# MT32Pi_lite.net
KiCad netlist of a schematic drawn in Altium Designer
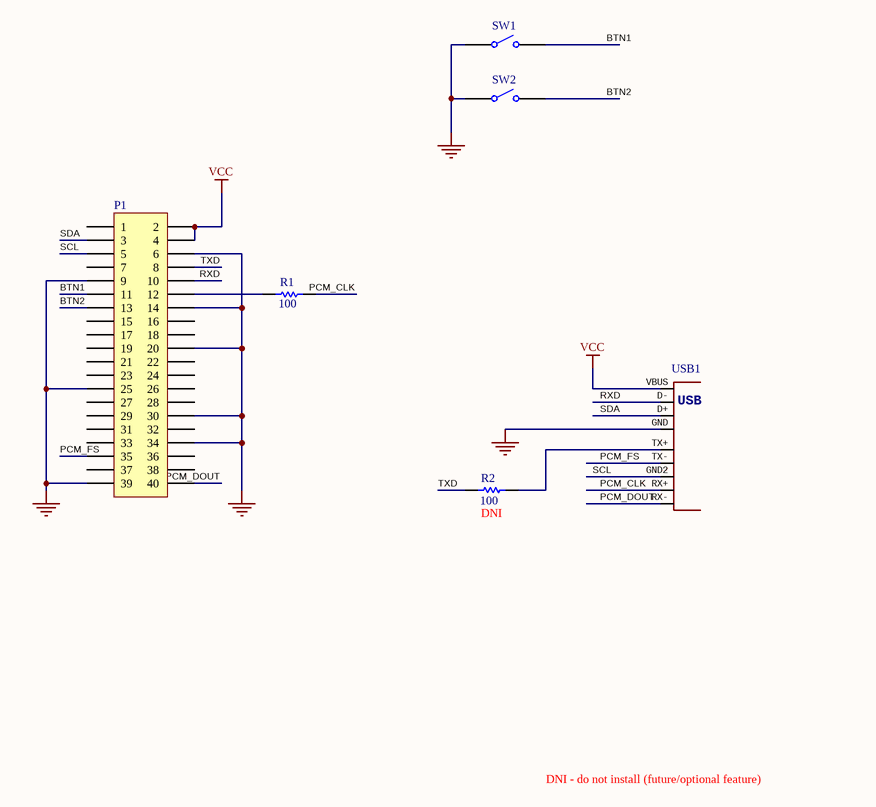
[diagram p0: MT32Pi_lite.SchDoc]

(export (version "E")
  (design (tool "Eeschema 10.0.6"))
  (components
    (comp (ref "P1")
      (value "Header 20X2")
      (footprint "HDR20x2")
      (description "Header, 20-Pin, Dual row")
      (fields (field (name "PUBLISHER") "Altium Limited"))
      (libsource (lib "Miscellaneous Connectors") (part "Header 20X2"))
    )
    (comp (ref "R1")
      (value "100")
      (footprint "R0805")
      (fields (field (name "PUBLISHER") "Altium Limited"))
      (libsource (lib "lib") (part "R0805"))
    )
    (comp (ref "R2")
      (value "100")
      (footprint "R0805 - DNI")
      (fields (field (name "PUBLISHER") "Altium Limited"))
      (libsource (lib "lib") (part "R0805 - DNI"))
    )
    (comp (ref "SW1")
      (value "Tact_60X35")
      (footprint "TACT_60X35")
      (description "Tact 6.0mm X 3.5mm")
      (fields (field (name "PARTNUMBER") "434111050826"))
      (libsource (lib "lib") (part "Tact_60X35"))
    )
    (comp (ref "SW2")
      (value "Tact_60X35")
      (footprint "TACT_60X35")
      (description "Tact 6.0mm X 3.5mm")
      (fields (field (name "PARTNUMBER") "434111050826"))
      (libsource (lib "lib") (part "Tact_60X35"))
    )
    (comp (ref "USB1")
      (value "USBA30-PTH")
      (footprint "USB3-A-M-PTH")
      (fields (field (name "USB") "USB"))
      (libsource (lib "lib") (part "USBA30-PTH"))
    )
  )
  (nets
    (net (code "1") (name "/BTN1") (class "Default")
      (node (ref "P1") (pin "11") (pinfunction "11_11") (pintype "passive"))
      (node (ref "SW1") (pin "2") (pinfunction "2_2") (pintype "passive"))
    )
    (net (code "2") (name "/BTN2") (class "Default")
      (node (ref "P1") (pin "13") (pinfunction "13_13") (pintype "passive"))
      (node (ref "SW2") (pin "2") (pinfunction "2_2") (pintype "passive"))
    )
    (net (code "3") (name "/PCM_CLK") (class "Default")
      (node (ref "R1") (pin "1") (pinfunction "1_1") (pintype "passive"))
      (node (ref "USB1") (pin "RX+") (pinfunction "RX+_RX+") (pintype "passive"))
    )
    (net (code "4") (name "/PCM_DOUT") (class "Default")
      (node (ref "P1") (pin "40") (pinfunction "40_40") (pintype "passive"))
      (node (ref "USB1") (pin "RX-") (pinfunction "RX-_RX-") (pintype "passive"))
    )
    (net (code "5") (name "/PCM_FS") (class "Default")
      (node (ref "P1") (pin "35") (pinfunction "35_35") (pintype "passive"))
      (node (ref "USB1") (pin "TX-") (pinfunction "TX-_TX-") (pintype "passive"))
    )
    (net (code "6") (name "/RXD") (class "Default")
      (node (ref "P1") (pin "10") (pinfunction "10_10") (pintype "passive"))
      (node (ref "USB1") (pin "D-") (pinfunction "D-_D-") (pintype "passive"))
    )
    (net (code "7") (name "/SCL") (class "Default")
      (node (ref "P1") (pin "5") (pinfunction "5_5") (pintype "passive"))
      (node (ref "USB1") (pin "GND2") (pinfunction "GND2_GND2") (pintype "passive"))
    )
    (net (code "8") (name "/SDA") (class "Default")
      (node (ref "P1") (pin "3") (pinfunction "3_3") (pintype "passive"))
      (node (ref "USB1") (pin "D+") (pinfunction "D+_D+") (pintype "passive"))
    )
    (net (code "9") (name "/TXD") (class "Default")
      (node (ref "P1") (pin "8") (pinfunction "8_8") (pintype "passive"))
      (node (ref "R2") (pin "1") (pinfunction "1_1") (pintype "passive"))
    )
    (net (code "10") (name "GND") (class "Default")
      (node (ref "P1") (pin "14") (pinfunction "14_14") (pintype "passive"))
      (node (ref "P1") (pin "20") (pinfunction "20_20") (pintype "passive"))
      (node (ref "P1") (pin "25") (pinfunction "25_25") (pintype "passive"))
      (node (ref "P1") (pin "30") (pinfunction "30_30") (pintype "passive"))
      (node (ref "P1") (pin "34") (pinfunction "34_34") (pintype "passive"))
      (node (ref "P1") (pin "39") (pinfunction "39_39") (pintype "passive"))
      (node (ref "P1") (pin "6") (pinfunction "6_6") (pintype "passive"))
      (node (ref "P1") (pin "9") (pinfunction "9_9") (pintype "passive"))
      (node (ref "SW1") (pin "1") (pinfunction "1_1") (pintype "passive"))
      (node (ref "SW2") (pin "1") (pinfunction "1_1") (pintype "passive"))
      (node (ref "USB1") (pin "GND") (pinfunction "GND_GND") (pintype "passive"))
    )
    (net (code "11") (name "Net-(P1-Pad12)") (class "Default")
      (node (ref "P1") (pin "12") (pinfunction "12_12") (pintype "passive"))
      (node (ref "R1") (pin "2") (pinfunction "2_2") (pintype "passive"))
    )
    (net (code "12") (name "Net-(R2-Pad2)") (class "Default")
      (node (ref "R2") (pin "2") (pinfunction "2_2") (pintype "passive"))
      (node (ref "USB1") (pin "TX+") (pinfunction "TX+_TX+") (pintype "passive"))
    )
    (net (code "13") (name "VCC") (class "Default")
      (node (ref "P1") (pin "2") (pinfunction "2_2") (pintype "passive"))
      (node (ref "P1") (pin "4") (pinfunction "4_4") (pintype "passive"))
      (node (ref "USB1") (pin "VBUS") (pinfunction "VBUS_VBUS") (pintype "passive"))
    )
    (net (code "14") (name "unconnected-(P1-Pad1)") (class "Default")
      (node (ref "P1") (pin "1") (pinfunction "1_1") (pintype "passive"))
    )
    (net (code "15") (name "unconnected-(P1-Pad7)") (class "Default")
      (node (ref "P1") (pin "7") (pinfunction "7_7") (pintype "passive"))
    )
    (net (code "16") (name "unconnected-(P1-Pad15)") (class "Default")
      (node (ref "P1") (pin "15") (pinfunction "15_15") (pintype "passive"))
    )
    (net (code "17") (name "unconnected-(P1-Pad16)") (class "Default")
      (node (ref "P1") (pin "16") (pinfunction "16_16") (pintype "passive"))
    )
    (net (code "18") (name "unconnected-(P1-Pad17)") (class "Default")
      (node (ref "P1") (pin "17") (pinfunction "17_17") (pintype "passive"))
    )
    (net (code "19") (name "unconnected-(P1-Pad18)") (class "Default")
      (node (ref "P1") (pin "18") (pinfunction "18_18") (pintype "passive"))
    )
    (net (code "20") (name "unconnected-(P1-Pad19)") (class "Default")
      (node (ref "P1") (pin "19") (pinfunction "19_19") (pintype "passive"))
    )
    (net (code "21") (name "unconnected-(P1-Pad21)") (class "Default")
      (node (ref "P1") (pin "21") (pinfunction "21_21") (pintype "passive"))
    )
    (net (code "22") (name "unconnected-(P1-Pad22)") (class "Default")
      (node (ref "P1") (pin "22") (pinfunction "22_22") (pintype "passive"))
    )
    (net (code "23") (name "unconnected-(P1-Pad23)") (class "Default")
      (node (ref "P1") (pin "23") (pinfunction "23_23") (pintype "passive"))
    )
    (net (code "24") (name "unconnected-(P1-Pad24)") (class "Default")
      (node (ref "P1") (pin "24") (pinfunction "24_24") (pintype "passive"))
    )
    (net (code "25") (name "unconnected-(P1-Pad26)") (class "Default")
      (node (ref "P1") (pin "26") (pinfunction "26_26") (pintype "passive"))
    )
    (net (code "26") (name "unconnected-(P1-Pad27)") (class "Default")
      (node (ref "P1") (pin "27") (pinfunction "27_27") (pintype "passive"))
    )
    (net (code "27") (name "unconnected-(P1-Pad28)") (class "Default")
      (node (ref "P1") (pin "28") (pinfunction "28_28") (pintype "passive"))
    )
    (net (code "28") (name "unconnected-(P1-Pad29)") (class "Default")
      (node (ref "P1") (pin "29") (pinfunction "29_29") (pintype "passive"))
    )
    (net (code "29") (name "unconnected-(P1-Pad31)") (class "Default")
      (node (ref "P1") (pin "31") (pinfunction "31_31") (pintype "passive"))
    )
    (net (code "30") (name "unconnected-(P1-Pad32)") (class "Default")
      (node (ref "P1") (pin "32") (pinfunction "32_32") (pintype "passive"))
    )
    (net (code "31") (name "unconnected-(P1-Pad33)") (class "Default")
      (node (ref "P1") (pin "33") (pinfunction "33_33") (pintype "passive"))
    )
    (net (code "32") (name "unconnected-(P1-Pad36)") (class "Default")
      (node (ref "P1") (pin "36") (pinfunction "36_36") (pintype "passive"))
    )
    (net (code "33") (name "unconnected-(P1-Pad37)") (class "Default")
      (node (ref "P1") (pin "37") (pinfunction "37_37") (pintype "passive"))
    )
    (net (code "34") (name "unconnected-(P1-Pad38)") (class "Default")
      (node (ref "P1") (pin "38") (pinfunction "38_38") (pintype "passive"))
    )
  )
)
